# Sheet1.net
KiCad netlist of a schematic drawn in Altium Designer
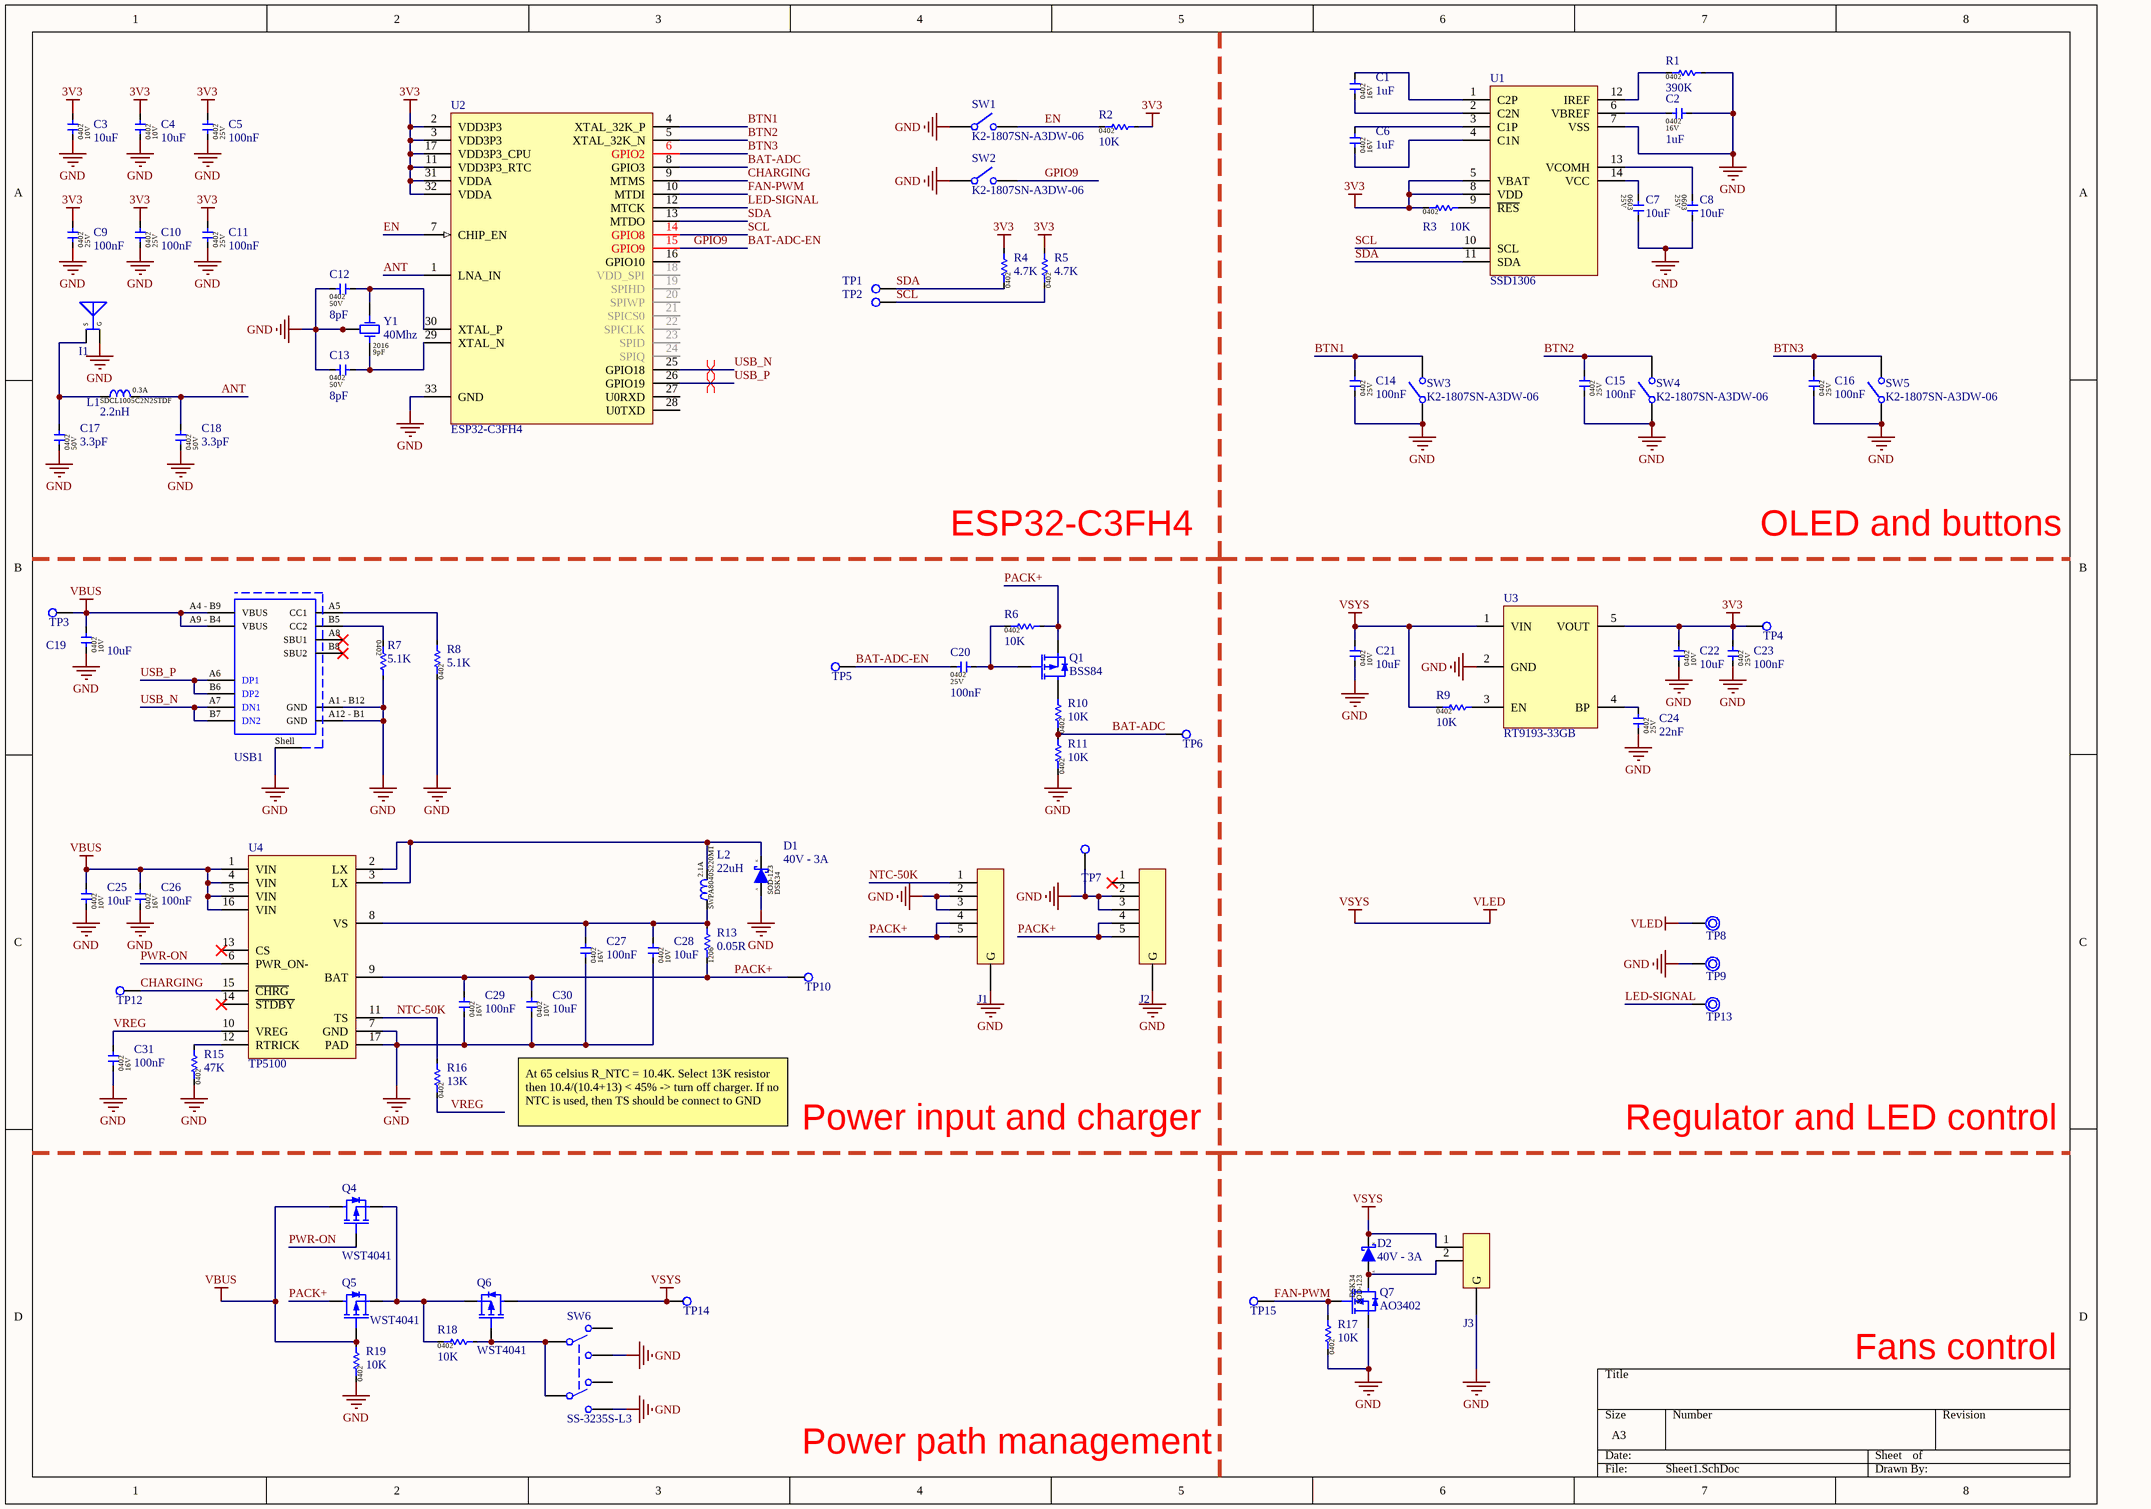
[diagram p0: Sheet1.SchDoc]

(export (version "E")
  (design (tool "Eeschema 10.0.6"))
  (components
    (comp (ref "C1")
      (value "1uF")
      (footprint "CAP-0402")
      (description "1uF ±10% 16V X5R 0402 Multilayer Ceramic Capacitors MLCC - SMD/SMT RoHS")
      (fields (field (name "MANUFACTURE PART") "0402X105K160CT") (field (name "VOLTAGE") "16V"))
      (libsource (lib "Capacitor Database") (part "Cap-non-polarized"))
    )
    (comp (ref "C2")
      (value "1uF")
      (footprint "CAP-0402")
      (description "1uF ±10% 16V X5R 0402 Multilayer Ceramic Capacitors MLCC - SMD/SMT RoHS")
      (fields (field (name "MANUFACTURE PART") "0402X105K160CT") (field (name "VOLTAGE") "16V"))
      (libsource (lib "Capacitor Database") (part "Cap-non-polarized"))
    )
    (comp (ref "C3")
      (value "10uF")
      (footprint "CAP-0402")
      (description "10V 10uF X5R ±20% 0402 Multilayer Ceramic Capacitors MLCC - SMD/SMT ROHS")
      (fields (field (name "MANUFACTURE PART") "CL05A106MP5NUNC") (field (name "VOLTAGE") "10V"))
      (libsource (lib "Capacitor Database") (part "Cap-non-polarized"))
    )
    (comp (ref "C4")
      (value "10uF")
      (footprint "CAP-0402")
      (description "10V 10uF X5R ±20% 0402 Multilayer Ceramic Capacitors MLCC - SMD/SMT ROHS")
      (fields (field (name "MANUFACTURE PART") "CL05A106MP5NUNC") (field (name "VOLTAGE") "10V"))
      (libsource (lib "Capacitor Database") (part "Cap-non-polarized"))
    )
    (comp (ref "C5")
      (value "100nF")
      (footprint "CAP-0402")
      (description "100nF ±10% 25V X5R 0402 Multilayer Ceramic Capacitors MLCC - SMD/SMT RoHS")
      (fields (field (name "MANUFACTURE PART") "0402X104K250CT") (field (name "VOLTAGE") "25V"))
      (libsource (lib "Capacitor Database") (part "Cap-non-polarized"))
    )
    (comp (ref "C6")
      (value "1uF")
      (footprint "CAP-0402")
      (description "1uF ±10% 16V X5R 0402 Multilayer Ceramic Capacitors MLCC - SMD/SMT RoHS")
      (fields (field (name "MANUFACTURE PART") "0402X105K160CT") (field (name "VOLTAGE") "16V"))
      (libsource (lib "Capacitor Database") (part "Cap-non-polarized"))
    )
    (comp (ref "C7")
      (value "10uF")
      (footprint "CAP-0603")
      (description "25V 10uF X5R ±20% 0603 Multilayer Ceramic Capacitors MLCC - SMD/SMT ROHS")
      (fields (field (name "MANUFACTURE PART") "CL10A106MA8NRNC") (field (name "VOLTAGE") "25V"))
      (libsource (lib "Capacitor Database") (part "Cap-non-polarized"))
    )
    (comp (ref "C8")
      (value "10uF")
      (footprint "CAP-0603")
      (description "25V 10uF X5R ±20% 0603 Multilayer Ceramic Capacitors MLCC - SMD/SMT ROHS")
      (fields (field (name "MANUFACTURE PART") "CL10A106MA8NRNC") (field (name "VOLTAGE") "25V"))
      (libsource (lib "Capacitor Database") (part "Cap-non-polarized"))
    )
    (comp (ref "C9")
      (value "100nF")
      (footprint "CAP-0402")
      (description "100nF ±10% 25V X5R 0402 Multilayer Ceramic Capacitors MLCC - SMD/SMT RoHS")
      (fields (field (name "MANUFACTURE PART") "0402X104K250CT") (field (name "VOLTAGE") "25V"))
      (libsource (lib "Capacitor Database") (part "Cap-non-polarized"))
    )
    (comp (ref "C10")
      (value "100nF")
      (footprint "CAP-0402")
      (description "100nF ±10% 25V X5R 0402 Multilayer Ceramic Capacitors MLCC - SMD/SMT RoHS")
      (fields (field (name "MANUFACTURE PART") "0402X104K250CT") (field (name "VOLTAGE") "25V"))
      (libsource (lib "Capacitor Database") (part "Cap-non-polarized"))
    )
    (comp (ref "C11")
      (value "100nF")
      (footprint "CAP-0402")
      (description "100nF ±10% 25V X5R 0402 Multilayer Ceramic Capacitors MLCC - SMD/SMT RoHS")
      (fields (field (name "MANUFACTURE PART") "0402X104K250CT") (field (name "VOLTAGE") "25V"))
      (libsource (lib "Capacitor Database") (part "Cap-non-polarized"))
    )
    (comp (ref "C12")
      (value "8pF")
      (footprint "CAP-0402")
      (description "8 pF ±0.5pF 50V Ceramic Capacitor C0G, NP0 0402 (1005 Metric)")
      (fields (field (name "MANUFACTURE PART") "CL05C080DB5NNNC") (field (name "VOLTAGE") "50V"))
      (libsource (lib "Capacitor Database") (part "Cap-non-polarized"))
    )
    (comp (ref "C13")
      (value "8pF")
      (footprint "CAP-0402")
      (description "8 pF ±0.5pF 50V Ceramic Capacitor C0G, NP0 0402 (1005 Metric)")
      (fields (field (name "MANUFACTURE PART") "CL05C080DB5NNNC") (field (name "VOLTAGE") "50V"))
      (libsource (lib "Capacitor Database") (part "Cap-non-polarized"))
    )
    (comp (ref "C14")
      (value "100nF")
      (footprint "CAP-0402")
      (description "100nF ±10% 25V X5R 0402 Multilayer Ceramic Capacitors MLCC - SMD/SMT RoHS")
      (fields (field (name "MANUFACTURE PART") "0402X104K250CT") (field (name "VOLTAGE") "25V"))
      (libsource (lib "Capacitor Database") (part "Cap-non-polarized"))
    )
    (comp (ref "C15")
      (value "100nF")
      (footprint "CAP-0402")
      (description "100nF ±10% 25V X5R 0402 Multilayer Ceramic Capacitors MLCC - SMD/SMT RoHS")
      (fields (field (name "MANUFACTURE PART") "0402X104K250CT") (field (name "VOLTAGE") "25V"))
      (libsource (lib "Capacitor Database") (part "Cap-non-polarized"))
    )
    (comp (ref "C16")
      (value "100nF")
      (footprint "CAP-0402")
      (description "100nF ±10% 25V X5R 0402 Multilayer Ceramic Capacitors MLCC - SMD/SMT RoHS")
      (fields (field (name "MANUFACTURE PART") "0402X104K250CT") (field (name "VOLTAGE") "25V"))
      (libsource (lib "Capacitor Database") (part "Cap-non-polarized"))
    )
    (comp (ref "C17")
      (value "3.3pF")
      (footprint "CAP-0402")
      (description "3.3pF ±0.25pF 50V NP0(C0G) 0402 Multilayer Ceramic Capacitors MLCC - SMD/SMT RoHS")
      (fields (field (name "MANUFACTURE PART") "0402N3R3C500CT") (field (name "VOLTAGE") "50V"))
      (libsource (lib "Capacitor Database") (part "Cap-non-polarized"))
    )
    (comp (ref "C18")
      (value "3.3pF")
      (footprint "CAP-0402")
      (description "3.3pF ±0.25pF 50V NP0(C0G) 0402 Multilayer Ceramic Capacitors MLCC - SMD/SMT RoHS")
      (fields (field (name "MANUFACTURE PART") "0402N3R3C500CT") (field (name "VOLTAGE") "50V"))
      (libsource (lib "Capacitor Database") (part "Cap-non-polarized"))
    )
    (comp (ref "C19")
      (value "10uF")
      (footprint "CAP-0402")
      (description "10V 10uF X5R ±20% 0402 Multilayer Ceramic Capacitors MLCC - SMD/SMT ROHS")
      (fields (field (name "MANUFACTURE PART") "CL05A106MP5NUNC") (field (name "VOLTAGE") "10V"))
      (libsource (lib "Capacitor Database") (part "Cap-non-polarized"))
    )
    (comp (ref "C20")
      (value "100nF")
      (footprint "CAP-0402")
      (description "100nF ±10% 25V X5R 0402 Multilayer Ceramic Capacitors MLCC - SMD/SMT RoHS")
      (fields (field (name "MANUFACTURE PART") "0402X104K250CT") (field (name "VOLTAGE") "25V"))
      (libsource (lib "Capacitor Database") (part "Cap-non-polarized"))
    )
    (comp (ref "C21")
      (value "10uF")
      (footprint "CAP-0402")
      (description "10V 10uF X5R ±20% 0402 Multilayer Ceramic Capacitors MLCC - SMD/SMT ROHS")
      (fields (field (name "MANUFACTURE PART") "CL05A106MP5NUNC") (field (name "VOLTAGE") "10V"))
      (libsource (lib "Capacitor Database") (part "Cap-non-polarized"))
    )
    (comp (ref "C22")
      (value "10uF")
      (footprint "CAP-0402")
      (description "10V 10uF X5R ±20% 0402 Multilayer Ceramic Capacitors MLCC - SMD/SMT ROHS")
      (fields (field (name "MANUFACTURE PART") "CL05A106MP5NUNC") (field (name "VOLTAGE") "10V"))
      (libsource (lib "Capacitor Database") (part "Cap-non-polarized"))
    )
    (comp (ref "C23")
      (value "100nF")
      (footprint "CAP-0402")
      (description "100nF ±10% 25V X5R 0402 Multilayer Ceramic Capacitors MLCC - SMD/SMT RoHS")
      (fields (field (name "MANUFACTURE PART") "0402X104K250CT") (field (name "VOLTAGE") "25V"))
      (libsource (lib "Capacitor Database") (part "Cap-non-polarized"))
    )
    (comp (ref "C24")
      (value "22nF")
      (footprint "CAP-0402")
      (description "22nF ±10% 25V X7R 0402 Multilayer Ceramic Capacitors MLCC - SMD/SMT RoHS")
      (fields (field (name "MANUFACTURE PART") "0402B223K250CT") (field (name "VOLTAGE") "25V"))
      (libsource (lib "Capacitor Database") (part "Cap-non-polarized"))
    )
    (comp (ref "C25")
      (value "10uF")
      (footprint "CAP-0402")
      (description "10V 10uF X5R ±20% 0402 Multilayer Ceramic Capacitors MLCC - SMD/SMT ROHS")
      (fields (field (name "MANUFACTURE PART") "CL05A106MP5NUNC") (field (name "VOLTAGE") "10V"))
      (libsource (lib "Capacitor Database") (part "Cap-non-polarized"))
    )
    (comp (ref "C26")
      (value "100nF")
      (footprint "CAP-0402")
      (description "100nF ±10% 16V X7R 0402 Multilayer Ceramic Capacitors MLCC - SMD/SMT RoHS")
      (fields (field (name "MANUFACTURE PART") "0402B104K160CT") (field (name "VOLTAGE") "16V"))
      (libsource (lib "Capacitor Database") (part "Cap-non-polarized"))
    )
    (comp (ref "C27")
      (value "100nF")
      (footprint "CAP-0402")
      (description "100nF ±10% 16V X7R 0402 Multilayer Ceramic Capacitors MLCC - SMD/SMT RoHS")
      (fields (field (name "MANUFACTURE PART") "0402B104K160CT") (field (name "VOLTAGE") "16V"))
      (libsource (lib "Capacitor Database") (part "Cap-non-polarized"))
    )
    (comp (ref "C28")
      (value "10uF")
      (footprint "CAP-0402")
      (description "10V 10uF X5R ±20% 0402 Multilayer Ceramic Capacitors MLCC - SMD/SMT ROHS")
      (fields (field (name "MANUFACTURE PART") "CL05A106MP5NUNC") (field (name "VOLTAGE") "10V"))
      (libsource (lib "Capacitor Database") (part "Cap-non-polarized"))
    )
    (comp (ref "C29")
      (value "100nF")
      (footprint "CAP-0402")
      (description "100nF ±10% 16V X7R 0402 Multilayer Ceramic Capacitors MLCC - SMD/SMT RoHS")
      (fields (field (name "MANUFACTURE PART") "0402B104K160CT") (field (name "VOLTAGE") "16V"))
      (libsource (lib "Capacitor Database") (part "Cap-non-polarized"))
    )
    (comp (ref "C30")
      (value "10uF")
      (footprint "CAP-0402")
      (description "10V 10uF X5R ±20% 0402 Multilayer Ceramic Capacitors MLCC - SMD/SMT ROHS")
      (fields (field (name "MANUFACTURE PART") "CL05A106MP5NUNC") (field (name "VOLTAGE") "10V"))
      (libsource (lib "Capacitor Database") (part "Cap-non-polarized"))
    )
    (comp (ref "C31")
      (value "100nF")
      (footprint "CAP-0402")
      (description "100nF ±10% 16V X7R 0402 Multilayer Ceramic Capacitors MLCC - SMD/SMT RoHS")
      (fields (field (name "MANUFACTURE PART") "0402B104K160CT") (field (name "VOLTAGE") "16V"))
      (libsource (lib "Capacitor Database") (part "Cap-non-polarized"))
    )
    (comp (ref "D1")
      (value "40V - 3A")
      (footprint "SOD123")
      (description "40V 3A 550mV @ 3A SOD-123 Schottky Barrier Diodes (SBD) RoHS")
      (fields (field (name "MANUFACTURE PART") "DSK34"))
      (libsource (lib "Diode Database") (part "Schottky diode"))
    )
    (comp (ref "D2")
      (value "40V - 3A")
      (footprint "SOD123")
      (description "40V 3A 550mV @ 3A SOD-123 Schottky Barrier Diodes (SBD) RoHS")
      (fields (field (name "MANUFACTURE PART") "DSK34"))
      (libsource (lib "Diode Database") (part "Schottky diode"))
    )
    (comp (ref "I1")
      (value "AN043")
      (footprint "PCB antenna - AN043")
      (description ".Description")
      (libsource (lib "Connectors, Misc") (part "Ipex"))
    )
    (comp (ref "J1")
      (value "20037WR-05")
      (footprint "HY-2.0-5Pin-SMT")
      (description ".Description")
      (libsource (lib "Connectors, Misc") (part "Conn-5P_PAD"))
    )
    (comp (ref "J2")
      (value "20037WR-05")
      (footprint "HY-2.0-5Pin-SMT")
      (description ".Description")
      (libsource (lib "Connectors, Misc") (part "Conn-5P_PAD"))
    )
    (comp (ref "J3")
      (value "ZX-XH2.54-2PLT")
      (footprint "XH-2.54-2Pin-SMT-vertical")
      (description ".Description")
      (libsource (lib "Connectors, Misc") (part "Conn-2P_PAD"))
    )
    (comp (ref "L1")
      (value "2.2nH")
      (footprint "L-0402")
      (description "300mA 2.2nH 200mΩ 0402 Inductors (SMD) ROHS")
      (fields (field (name "MANUFACTURE PART") "SDCL1005C2N2STDF"))
      (libsource (lib "Inductor Database") (part "Inductor"))
    )
    (comp (ref "L2")
      (value "22uH")
      (footprint "IND-8040")
      (description "Inductor 22uH ±20% 2.1A, 8.0x8.0x4.0")
      (fields (field (name "MANUFACTURE PART") "SWPA8040S220MT"))
      (libsource (lib "") (part "Inductor_1"))
    )
    (comp (ref "Q1")
      (value "BSS84")
      (footprint "SOT23-3")
      (description "60V 0.23A 3.5Ω@10V,230mA 350mW 1V@230mA 1PCSPChannel SOT-23 MOSFETs ROHS")
      (libsource (lib "Transistor Database") (part "Generic P-Mosfet"))
    )
    (comp (ref "Q4")
      (value "WST4041")
      (footprint "SOT23-3")
      (description "1.4W 40V 6A 2.2V 250uA P Channel 0.04Ω 3A,10V SOT-23(SOT-23-3) MOSFETs ROHS")
      (libsource (lib "Transistor Database") (part "Generic P-Mosfet"))
    )
    (comp (ref "Q5")
      (value "WST4041")
      (footprint "SOT23-3")
      (description "1.4W 40V 6A 2.2V 250uA P Channel 0.04Ω 3A,10V SOT-23(SOT-23-3) MOSFETs ROHS")
      (libsource (lib "Transistor Database") (part "Generic P-Mosfet"))
    )
    (comp (ref "Q6")
      (value "WST4041")
      (footprint "SOT23-3")
      (description "1.4W 40V 6A 2.2V 250uA P Channel 0.04Ω 3A,10V SOT-23(SOT-23-3) MOSFETs ROHS")
      (libsource (lib "Transistor Database") (part "Generic P-Mosfet"))
    )
    (comp (ref "Q7")
      (value "AO3402")
      (footprint "SOT23-3")
      (description "N-Channel 30V 4A 1.4V @ 250uA 55mΩ @ 4A,10V 1.4W SOT-23 MOSFETs RoHS")
      (libsource (lib "Transistor Database") (part "Generic N-Mosfet"))
    )
    (comp (ref "R1")
      (value "390K")
      (footprint "RES-0402")
      (description "±1% 1/16W 50V ±100ppm/℃ -55℃~+155℃ 390kΩ 0402 Chip Resistor - Surface Mount ROHS")
      (fields (field (name "MANUFACTURE PART") "WR04X3903FTL"))
      (libsource (lib "Resistor Database") (part "Resistor"))
    )
    (comp (ref "R2")
      (value "10K")
      (footprint "RES-0402")
      (description "10kΩ ±1% 1/16W ±100ppm/℃ 0402 Chip Resistor - Surface Mount RoHS")
      (fields (field (name "MANUFACTURE PART") "WR04X1002FTL"))
      (libsource (lib "Resistor Database") (part "Resistor"))
    )
    (comp (ref "R3")
      (value "10K")
      (footprint "RES-0402")
      (description "10kΩ ±1% 1/16W ±100ppm/℃ 0402 Chip Resistor - Surface Mount RoHS")
      (fields (field (name "MANUFACTURE PART") "WR04X1002FTL"))
      (libsource (lib "Resistor Database") (part "Resistor"))
    )
    (comp (ref "R4")
      (value "4.7K")
      (footprint "RES-0402")
      (description "4.7kΩ ±1% 1/16W ±100ppm/℃ 0402 Chip Resistor - Surface Mount RoHS")
      (fields (field (name "MANUFACTURE PART") "WR04X4701FTL"))
      (libsource (lib "Resistor Database") (part "Resistor"))
    )
    (comp (ref "R5")
      (value "4.7K")
      (footprint "RES-0402")
      (description "4.7kΩ ±1% 1/16W ±100ppm/℃ 0402 Chip Resistor - Surface Mount RoHS")
      (fields (field (name "MANUFACTURE PART") "WR04X4701FTL"))
      (libsource (lib "Resistor Database") (part "Resistor"))
    )
    (comp (ref "R6")
      (value "10K")
      (footprint "RES-0402")
      (description "10kΩ ±1% 1/16W ±100ppm/℃ 0402 Chip Resistor - Surface Mount RoHS")
      (fields (field (name "MANUFACTURE PART") "WR04X1002FTL"))
      (libsource (lib "Resistor Database") (part "Resistor"))
    )
    (comp (ref "R7")
      (value "5.1K")
      (footprint "RES-0402")
      (description "5.1kΩ ±1% 1/16W ±100ppm/℃ 0402 Chip Resistor - Surface Mount RoHS")
      (fields (field (name "MANUFACTURE PART") "WR04X5101FTL"))
      (libsource (lib "Resistor Database") (part "Resistor"))
    )
    (comp (ref "R8")
      (value "5.1K")
      (footprint "RES-0402")
      (description "5.1kΩ ±1% 1/16W ±100ppm/℃ 0402 Chip Resistor - Surface Mount RoHS")
      (fields (field (name "MANUFACTURE PART") "WR04X5101FTL"))
      (libsource (lib "Resistor Database") (part "Resistor"))
    )
    (comp (ref "R9")
      (value "10K")
      (footprint "RES-0402")
      (description "10kΩ ±1% 1/16W ±100ppm/℃ 0402 Chip Resistor - Surface Mount RoHS")
      (fields (field (name "MANUFACTURE PART") "WR04X1002FTL"))
      (libsource (lib "Resistor Database") (part "Resistor"))
    )
    (comp (ref "R10")
      (value "10K")
      (footprint "RES-0402")
      (description "10kΩ ±1% 1/16W ±100ppm/℃ 0402 Chip Resistor - Surface Mount RoHS")
      (fields (field (name "MANUFACTURE PART") "WR04X1002FTL"))
      (libsource (lib "Resistor Database") (part "Resistor"))
    )
    (comp (ref "R11")
      (value "10K")
      (footprint "RES-0402")
      (description "10kΩ ±1% 1/16W ±100ppm/℃ 0402 Chip Resistor - Surface Mount RoHS")
      (fields (field (name "MANUFACTURE PART") "WR04X1002FTL"))
      (libsource (lib "Resistor Database") (part "Resistor"))
    )
    (comp (ref "R13")
      (value "0.05R")
      (footprint "RES-1206")
      (description "±1% 0.05Ω 1W ±50ppm/℃ 1206 Current Sense Resistors/Shunt Resistors ROHS")
      (fields (field (name "MANUFACTURE PART") "LR1206-21R050F4"))
      (libsource (lib "Resistor Database") (part "Resistor"))
    )
    (comp (ref "R15")
      (value "47K")
      (footprint "RES-0402")
      (description "62.5mW Thick Film Resistors ±100ppm/℃ ±1% 47kΩ 0402 Chip Resistor - Surface Mount ROHS")
      (fields (field (name "MANUFACTURE PART") "RC0402FR-0747KL"))
      (libsource (lib "Resistor Database") (part "Resistor"))
    )
    (comp (ref "R16")
      (value "13K")
      (footprint "RES-0402")
      (description "62.5mW Thick Film Resistors ±100ppm/℃ ±1% 13kΩ 0402 Chip Resistor - Surface Mount ROHS")
      (fields (field (name "MANUFACTURE PART") "RC0402FR-0713KL"))
      (libsource (lib "Resistor Database") (part "Resistor"))
    )
    (comp (ref "R17")
      (value "10K")
      (footprint "RES-0402")
      (description "10kΩ ±1% 1/16W ±100ppm/℃ 0402 Chip Resistor - Surface Mount RoHS")
      (fields (field (name "MANUFACTURE PART") "WR04X1002FTL"))
      (libsource (lib "Resistor Database") (part "Resistor"))
    )
    (comp (ref "R18")
      (value "10K")
      (footprint "RES-0402")
      (description "10kΩ ±1% 1/16W ±100ppm/℃ 0402 Chip Resistor - Surface Mount RoHS")
      (fields (field (name "MANUFACTURE PART") "WR04X1002FTL"))
      (libsource (lib "Resistor Database") (part "Resistor"))
    )
    (comp (ref "R19")
      (value "10K")
      (footprint "RES-0402")
      (description "10kΩ ±1% 1/16W ±100ppm/℃ 0402 Chip Resistor - Surface Mount RoHS")
      (fields (field (name "MANUFACTURE PART") "WR04X1002FTL"))
      (libsource (lib "Resistor Database") (part "Resistor"))
    )
    (comp (ref "SW1")
      (value "K2-1807SN-A3DW-06")
      (footprint "SW - TYPE 3")
      (description ".Description")
      (libsource (lib "Connectors, Misc") (part "Tactile Switch"))
    )
    (comp (ref "SW2")
      (value "K2-1807SN-A3DW-06")
      (footprint "SW - TYPE 3")
      (description ".Description")
      (libsource (lib "Connectors, Misc") (part "Tactile Switch"))
    )
    (comp (ref "SW3")
      (value "K2-1807SN-A3DW-06")
      (footprint "SW - TYPE 3")
      (description ".Description")
      (libsource (lib "Connectors, Misc") (part "Tactile Switch"))
    )
    (comp (ref "SW4")
      (value "K2-1807SN-A3DW-06")
      (footprint "SW - TYPE 3")
      (description ".Description")
      (libsource (lib "Connectors, Misc") (part "Tactile Switch"))
    )
    (comp (ref "SW5")
      (value "K2-1807SN-A3DW-06")
      (footprint "SW - TYPE 3")
      (description ".Description")
      (libsource (lib "Connectors, Misc") (part "Tactile Switch"))
    )
    (comp (ref "SW6")
      (value "SS-3235S-L3")
      (footprint "DPDT - type 1")
      (description ".Description")
      (libsource (lib "Connectors, Misc") (part "DPDT switch"))
    )
    (comp (ref "TP1")
      (value "Test point")
      (footprint "Test point")
      (description ".Description")
      (libsource (lib "Connectors, Misc") (part "Test point"))
    )
    (comp (ref "TP2")
      (value "Test point")
      (footprint "Test point")
      (description ".Description")
      (libsource (lib "Connectors, Misc") (part "Test point"))
    )
    (comp (ref "TP3")
      (value "Test point")
      (footprint "Test point")
      (description ".Description")
      (libsource (lib "Connectors, Misc") (part "Test point"))
    )
    (comp (ref "TP4")
      (value "Test point")
      (footprint "Test point")
      (description ".Description")
      (libsource (lib "Connectors, Misc") (part "Test point"))
    )
    (comp (ref "TP5")
      (value "Test point")
      (footprint "Test point")
      (description ".Description")
      (libsource (lib "Connectors, Misc") (part "Test point"))
    )
    (comp (ref "TP6")
      (value "Test point")
      (footprint "Test point")
      (description ".Description")
      (libsource (lib "Connectors, Misc") (part "Test point"))
    )
    (comp (ref "TP7")
      (value "Test point")
      (footprint "Test point")
      (description ".Description")
      (libsource (lib "Connectors, Misc") (part "Test point"))
    )
    (comp (ref "TP8")
      (value "Test point hole")
      (footprint "Test point hole")
      (description ".Description")
      (libsource (lib "Connectors, Misc") (part "Test point hole"))
    )
    (comp (ref "TP9")
      (value "Test point hole")
      (footprint "Test point hole")
      (description ".Description")
      (libsource (lib "Connectors, Misc") (part "Test point hole"))
    )
    (comp (ref "TP10")
      (value "Test point")
      (footprint "Test point")
      (description ".Description")
      (libsource (lib "Connectors, Misc") (part "Test point"))
    )
    (comp (ref "TP12")
      (value "Test point")
      (footprint "Test point")
      (description ".Description")
      (libsource (lib "Connectors, Misc") (part "Test point"))
    )
    (comp (ref "TP13")
      (value "Test point hole")
      (footprint "Test point hole")
      (description ".Description")
      (libsource (lib "Connectors, Misc") (part "Test point hole"))
    )
    (comp (ref "TP14")
      (value "Test point")
      (footprint "Test point")
      (description ".Description")
      (libsource (lib "Connectors, Misc") (part "Test point"))
    )
    (comp (ref "TP15")
      (value "Test point")
      (footprint "Test point")
      (description ".Description")
      (libsource (lib "Connectors, Misc") (part "Test point"))
    )
    (comp (ref "U1")
      (value "SSD1306")
      (footprint "OLED 0.91 14P")
      (description ".Description")
      (libsource (lib "Connectors, Misc") (part "OLED_0.91_SSD1306"))
    )
    (comp (ref "U2")
      (value "ESP32-C3FH4")
      (footprint "QFN32-5X5MM_PAD")
      (libsource (lib "IC Database") (part "ESP32-C3FH4"))
    )
    (comp (ref "U3")
      (value "RT9193-33GB")
      (footprint "SOT23-5")
      (description "Fixed 5.5V 3.3V 300mV @ 300mA SOT-23-5 Dropout Regulators(LDO) RoHS")
      (libsource (lib "Regulator Database") (part "RT9193"))
    )
    (comp (ref "U4")
      (value "TP5100")
      (footprint "QFN16-4X4MM_PAD")
      (description "1 and 2 cell Li-lon Battery Charger")
      (libsource (lib "IC Database") (part "TP5100"))
    )
    (comp (ref "USB1")
      (value "918-418K2023S40001")
      (footprint "1 FEMALE USB -C 16")
      (description ".Description")
      (libsource (lib "Connectors, Misc") (part "Female USB-C 16"))
    )
    (comp (ref "Y1")
      (value "40Mhz")
      (footprint "Crystal-2016")
      (description "40MHz 9pF SMD2016-4P Crystals ROHS")
      (fields (field (name "MANUFACTURE PART") "TZ1269D"))
      (libsource (lib "Osc Database") (part "XTAL-4 pin"))
    )
  )
  (nets
    (net (code "1") (name "/ANT") (class "Default")
      (node (ref "C18") (pin "2") (pinfunction "2_2") (pintype "passive"))
      (node (ref "L1") (pin "2") (pinfunction "2_2") (pintype "passive"))
      (node (ref "U2") (pin "1") (pinfunction "LNA_IN_1") (pintype "passive"))
    )
    (net (code "2") (name "/BAT-ADC") (class "Default")
      (node (ref "R10") (pin "1") (pinfunction "1_1") (pintype "passive"))
      (node (ref "R11") (pin "2") (pinfunction "2_2") (pintype "passive"))
      (node (ref "TP6") (pin "1") (pinfunction "1_1") (pintype "passive"))
      (node (ref "U2") (pin "8") (pinfunction "GPIO3_8") (pintype "passive"))
    )
    (net (code "3") (name "/BAT-ADC-EN") (class "Default")
      (node (ref "C20") (pin "1") (pinfunction "1_1") (pintype "passive"))
      (node (ref "SW2") (pin "2") (pintype "passive"))
      (node (ref "TP5") (pin "1") (pinfunction "1_1") (pintype "passive"))
      (node (ref "U2") (pin "15") (pinfunction "GPIO9_15") (pintype "passive"))
    )
    (net (code "4") (name "/BTN1") (class "Default")
      (node (ref "C14") (pin "2") (pinfunction "2_2") (pintype "passive"))
      (node (ref "SW3") (pin "2") (pintype "passive"))
      (node (ref "U2") (pin "4") (pinfunction "XTAL_32K_P_4") (pintype "passive"))
    )
    (net (code "5") (name "/BTN2") (class "Default")
      (node (ref "C15") (pin "2") (pinfunction "2_2") (pintype "passive"))
      (node (ref "SW4") (pin "2") (pintype "passive"))
      (node (ref "U2") (pin "5") (pinfunction "XTAL_32K_N_5") (pintype "passive"))
    )
    (net (code "6") (name "/BTN3") (class "Default")
      (node (ref "C16") (pin "2") (pinfunction "2_2") (pintype "passive"))
      (node (ref "SW5") (pin "2") (pintype "passive"))
      (node (ref "U2") (pin "6") (pinfunction "GPIO2_6") (pintype "passive"))
    )
    (net (code "7") (name "/CHARGING") (class "Default")
      (node (ref "TP12") (pin "1") (pinfunction "1_1") (pintype "passive"))
      (node (ref "U2") (pin "9") (pinfunction "MTMS_9") (pintype "passive"))
      (node (ref "U4") (pin "15") (pinfunction "~{CHRG}_15") (pintype "passive"))
    )
    (net (code "8") (name "/EN") (class "Default")
      (node (ref "R2") (pin "1") (pinfunction "1_1") (pintype "passive"))
      (node (ref "SW1") (pin "2") (pintype "passive"))
      (node (ref "U2") (pin "7") (pinfunction "CHIP_EN_7") (pintype "input"))
    )
    (net (code "9") (name "/FAN-PWM") (class "Default")
      (node (ref "Q7") (pin "1") (pinfunction "G_1") (pintype "passive"))
      (node (ref "R17") (pin "2") (pinfunction "2_2") (pintype "passive"))
      (node (ref "TP15") (pin "1") (pinfunction "1_1") (pintype "passive"))
      (node (ref "U2") (pin "10") (pinfunction "MTDI_10") (pintype "passive"))
    )
    (net (code "10") (name "/LED-SIGNAL") (class "Default")
      (node (ref "TP13") (pin "1") (pinfunction "1_1") (pintype "passive"))
      (node (ref "U2") (pin "12") (pinfunction "MTCK_12") (pintype "passive"))
    )
    (net (code "11") (name "/NTC-50K") (class "Default")
      (node (ref "J1") (pin "1") (pinfunction "1_1") (pintype "passive"))
      (node (ref "R16") (pin "2") (pinfunction "2_2") (pintype "passive"))
      (node (ref "U4") (pin "11") (pinfunction "TS_11") (pintype "passive"))
    )
    (net (code "12") (name "/PACK+") (class "Default")
      (node (ref "C29") (pin "2") (pinfunction "2_2") (pintype "passive"))
      (node (ref "C30") (pin "2") (pinfunction "2_2") (pintype "passive"))
      (node (ref "J1") (pin "4") (pinfunction "4_4") (pintype "passive"))
      (node (ref "J1") (pin "5") (pinfunction "5_5") (pintype "passive"))
      (node (ref "J2") (pin "4") (pinfunction "4_4") (pintype "passive"))
      (node (ref "J2") (pin "5") (pinfunction "5_5") (pintype "passive"))
      (node (ref "Q1") (pin "2") (pinfunction "S_2") (pintype "passive"))
      (node (ref "Q5") (pin "3") (pinfunction "D_3") (pintype "passive"))
      (node (ref "R13") (pin "1") (pinfunction "1_1") (pintype "passive"))
      (node (ref "R6") (pin "2") (pinfunction "2_2") (pintype "passive"))
      (node (ref "TP10") (pin "1") (pinfunction "1_1") (pintype "passive"))
      (node (ref "U4") (pin "9") (pinfunction "BAT_9") (pintype "passive"))
    )
    (net (code "13") (name "/PWR-ON") (class "Default")
      (node (ref "Q4") (pin "1") (pinfunction "G_1") (pintype "passive"))
      (node (ref "U4") (pin "6") (pinfunction "PWR_ON-_6") (pintype "passive"))
    )
    (net (code "14") (name "/SCL") (class "Default")
      (node (ref "R5") (pin "1") (pinfunction "1_1") (pintype "passive"))
      (node (ref "TP2") (pin "1") (pinfunction "1_1") (pintype "passive"))
      (node (ref "U1") (pin "10") (pinfunction "SCL_10") (pintype "passive"))
      (node (ref "U2") (pin "14") (pinfunction "GPIO8_14") (pintype "passive"))
    )
    (net (code "15") (name "/SDA") (class "Default")
      (node (ref "R4") (pin "1") (pinfunction "1_1") (pintype "passive"))
      (node (ref "TP1") (pin "1") (pinfunction "1_1") (pintype "passive"))
      (node (ref "U1") (pin "11") (pinfunction "SDA_11") (pintype "passive"))
      (node (ref "U2") (pin "13") (pinfunction "MTDO_13") (pintype "passive"))
    )
    (net (code "16") (name "/USB_N") (class "Default")
      (node (ref "U2") (pin "25") (pinfunction "GPIO18_25") (pintype "passive"))
      (node (ref "USB1") (pin "A7") (pinfunction "DN1_A7") (pintype "passive"))
      (node (ref "USB1") (pin "B7") (pinfunction "DN2_B7") (pintype "passive"))
    )
    (net (code "17") (name "/USB_P") (class "Default")
      (node (ref "U2") (pin "26") (pinfunction "GPIO19_26") (pintype "passive"))
      (node (ref "USB1") (pin "A6") (pinfunction "DP1_A6") (pintype "passive"))
      (node (ref "USB1") (pin "B6") (pinfunction "DP2_B6") (pintype "passive"))
    )
    (net (code "18") (name "/VREG") (class "Default")
      (node (ref "C31") (pin "2") (pinfunction "2_2") (pintype "passive"))
      (node (ref "R16") (pin "1") (pinfunction "1_1") (pintype "passive"))
      (node (ref "U4") (pin "10") (pinfunction "VREG_10") (pintype "passive"))
    )
    (net (code "19") (name "3V3") (class "Default")
      (node (ref "C10") (pin "2") (pinfunction "2_2") (pintype "passive"))
      (node (ref "C11") (pin "2") (pinfunction "2_2") (pintype "passive"))
      (node (ref "C22") (pin "2") (pinfunction "2_2") (pintype "passive"))
      (node (ref "C23") (pin "2") (pinfunction "2_2") (pintype "passive"))
      (node (ref "C3") (pin "2") (pinfunction "2_2") (pintype "passive"))
      (node (ref "C4") (pin "2") (pinfunction "2_2") (pintype "passive"))
      (node (ref "C5") (pin "2") (pinfunction "2_2") (pintype "passive"))
      (node (ref "C9") (pin "2") (pinfunction "2_2") (pintype "passive"))
      (node (ref "R2") (pin "2") (pinfunction "2_2") (pintype "passive"))
      (node (ref "R3") (pin "1") (pinfunction "1_1") (pintype "passive"))
      (node (ref "R4") (pin "2") (pinfunction "2_2") (pintype "passive"))
      (node (ref "R5") (pin "2") (pinfunction "2_2") (pintype "passive"))
      (node (ref "TP4") (pin "1") (pinfunction "1_1") (pintype "passive"))
      (node (ref "U1") (pin "5") (pinfunction "VBAT_5") (pintype "passive"))
      (node (ref "U1") (pin "8") (pinfunction "VDD_8") (pintype "passive"))
      (node (ref "U2") (pin "11") (pinfunction "VDD3P3_RTC_11") (pintype "passive"))
      (node (ref "U2") (pin "17") (pinfunction "VDD3P3_CPU_17") (pintype "passive"))
      (node (ref "U2") (pin "2") (pinfunction "VDD3P3_2") (pintype "passive"))
      (node (ref "U2") (pin "3") (pinfunction "VDD3P3_3") (pintype "passive"))
      (node (ref "U2") (pin "31") (pinfunction "VDDA_31") (pintype "passive"))
      (node (ref "U2") (pin "32") (pinfunction "VDDA_32") (pintype "passive"))
      (node (ref "U3") (pin "5") (pinfunction "VOUT_5") (pintype "passive"))
    )
    (net (code "20") (name "GND") (class "Default")
      (node (ref "C10") (pin "1") (pinfunction "1_1") (pintype "passive"))
      (node (ref "C11") (pin "1") (pinfunction "1_1") (pintype "passive"))
      (node (ref "C12") (pin "1") (pinfunction "1_1") (pintype "passive"))
      (node (ref "C13") (pin "1") (pinfunction "1_1") (pintype "passive"))
      (node (ref "C14") (pin "1") (pinfunction "1_1") (pintype "passive"))
      (node (ref "C15") (pin "1") (pinfunction "1_1") (pintype "passive"))
      (node (ref "C16") (pin "1") (pinfunction "1_1") (pintype "passive"))
      (node (ref "C17") (pin "1") (pinfunction "1_1") (pintype "passive"))
      (node (ref "C18") (pin "1") (pinfunction "1_1") (pintype "passive"))
      (node (ref "C19") (pin "1") (pinfunction "1_1") (pintype "passive"))
      (node (ref "C2") (pin "2") (pinfunction "2_2") (pintype "passive"))
      (node (ref "C21") (pin "1") (pinfunction "1_1") (pintype "passive"))
      (node (ref "C22") (pin "1") (pinfunction "1_1") (pintype "passive"))
      (node (ref "C23") (pin "1") (pinfunction "1_1") (pintype "passive"))
      (node (ref "C24") (pin "1") (pinfunction "1_1") (pintype "passive"))
      (node (ref "C25") (pin "1") (pinfunction "1_1") (pintype "passive"))
      (node (ref "C26") (pin "1") (pinfunction "1_1") (pintype "passive"))
      (node (ref "C27") (pin "1") (pinfunction "1_1") (pintype "passive"))
      (node (ref "C28") (pin "1") (pinfunction "1_1") (pintype "passive"))
      (node (ref "C29") (pin "1") (pinfunction "1_1") (pintype "passive"))
      (node (ref "C3") (pin "1") (pinfunction "1_1") (pintype "passive"))
      (node (ref "C30") (pin "1") (pinfunction "1_1") (pintype "passive"))
      (node (ref "C31") (pin "1") (pinfunction "1_1") (pintype "passive"))
      (node (ref "C4") (pin "1") (pinfunction "1_1") (pintype "passive"))
      (node (ref "C5") (pin "1") (pinfunction "1_1") (pintype "passive"))
      (node (ref "C7") (pin "2") (pinfunction "2_2") (pintype "passive"))
      (node (ref "C8") (pin "2") (pinfunction "2_2") (pintype "passive"))
      (node (ref "C9") (pin "1") (pinfunction "1_1") (pintype "passive"))
      (node (ref "D1") (pin "2") (pinfunction "Anode_2") (pintype "passive"))
      (node (ref "I1") (pin "0") (pinfunction "G_0") (pintype "passive"))
      (node (ref "J1") (pin "0") (pinfunction "G_0") (pintype "passive"))
      (node (ref "J1") (pin "2") (pinfunction "2_2") (pintype "passive"))
      (node (ref "J1") (pin "3") (pinfunction "3_3") (pintype "passive"))
      (node (ref "J2") (pin "0") (pinfunction "G_0") (pintype "passive"))
      (node (ref "J2") (pin "2") (pinfunction "2_2") (pintype "passive"))
      (node (ref "J2") (pin "3") (pinfunction "3_3") (pintype "passive"))
      (node (ref "J3") (pin "0") (pinfunction "G_0") (pintype "passive"))
      (node (ref "Q7") (pin "2") (pinfunction "S_2") (pintype "passive"))
      (node (ref "R1") (pin "2") (pinfunction "2_2") (pintype "passive"))
      (node (ref "R11") (pin "1") (pinfunction "1_1") (pintype "passive"))
      (node (ref "R15") (pin "1") (pinfunction "1_1") (pintype "passive"))
      (node (ref "R17") (pin "1") (pinfunction "1_1") (pintype "passive"))
      (node (ref "R19") (pin "1") (pinfunction "1_1") (pintype "passive"))
      (node (ref "R7") (pin "2") (pinfunction "2_2") (pintype "passive"))
      (node (ref "R8") (pin "1") (pinfunction "1_1") (pintype "passive"))
      (node (ref "SW1") (pin "1") (pintype "passive"))
      (node (ref "SW2") (pin "1") (pintype "passive"))
      (node (ref "SW3") (pin "1") (pintype "passive"))
      (node (ref "SW4") (pin "1") (pintype "passive"))
      (node (ref "SW5") (pin "1") (pintype "passive"))
      (node (ref "SW6") (pin "NO1") (pintype "passive"))
      (node (ref "SW6") (pin "NO2") (pintype "passive"))
      (node (ref "TP7") (pin "1") (pinfunction "1_1") (pintype "passive"))
      (node (ref "TP9") (pin "1") (pinfunction "1_1") (pintype "passive"))
      (node (ref "U1") (pin "7") (pinfunction "VSS_7") (pintype "passive"))
      (node (ref "U2") (pin "33") (pinfunction "GND_33") (pintype "passive"))
      (node (ref "U3") (pin "2") (pinfunction "GND_2") (pintype "passive"))
      (node (ref "U4") (pin "17") (pinfunction "PAD_17") (pintype "passive"))
      (node (ref "U4") (pin "7") (pinfunction "GND_7") (pintype "passive"))
      (node (ref "USB1") (pin "A12_-_B1") (pinfunction "GND_A12_-_B1") (pintype "passive"))
      (node (ref "USB1") (pin "A1_-_B12") (pinfunction "GND_A1_-_B12") (pintype "passive"))
      (node (ref "USB1") (pin "Shell") (pinfunction "Shield_Shell") (pintype "passive"))
      (node (ref "Y1") (pin "2") (pinfunction "GND_2") (pintype "power_in"))
      (node (ref "Y1") (pin "4") (pinfunction "GND_4") (pintype "power_in"))
    )
    (net (code "21") (name "Net-(D1-Cathode)") (class "Default")
      (node (ref "D1") (pin "1") (pinfunction "Cathode_1") (pintype "passive"))
      (node (ref "L2") (pin "2") (pinfunction "2_2") (pintype "passive"))
      (node (ref "U4") (pin "2") (pinfunction "LX_2") (pintype "passive"))
      (node (ref "U4") (pin "3") (pinfunction "LX_3") (pintype "passive"))
    )
    (net (code "22") (name "Net-(D2-Anode)") (class "Default")
      (node (ref "D2") (pin "2") (pinfunction "Anode_2") (pintype "passive"))
      (node (ref "J3") (pin "2") (pinfunction "2_2") (pintype "passive"))
      (node (ref "Q7") (pin "3") (pinfunction "D_3") (pintype "passive"))
    )
    (net (code "23") (name "Net-(I1-S)") (class "Default")
      (node (ref "C17") (pin "2") (pinfunction "2_2") (pintype "passive"))
      (node (ref "I1") (pin "1") (pinfunction "S_1") (pintype "passive"))
      (node (ref "L1") (pin "1") (pinfunction "1_1") (pintype "passive"))
    )
    (net (code "24") (name "Net-(Q1-D)") (class "Default")
      (node (ref "Q1") (pin "3") (pinfunction "D_3") (pintype "passive"))
      (node (ref "R10") (pin "2") (pinfunction "2_2") (pintype "passive"))
    )
    (net (code "25") (name "Net-(Q1-G)") (class "Default")
      (node (ref "C20") (pin "2") (pinfunction "2_2") (pintype "passive"))
      (node (ref "Q1") (pin "1") (pinfunction "G_1") (pintype "passive"))
      (node (ref "R6") (pin "1") (pinfunction "1_1") (pintype "passive"))
    )
    (net (code "26") (name "Net-(Q4-S)") (class "Default")
      (node (ref "Q4") (pin "2") (pinfunction "S_2") (pintype "passive"))
      (node (ref "Q5") (pin "2") (pinfunction "S_2") (pintype "passive"))
      (node (ref "Q6") (pin "2") (pinfunction "S_2") (pintype "passive"))
      (node (ref "R18") (pin "1") (pinfunction "1_1") (pintype "passive"))
    )
    (net (code "27") (name "Net-(Q6-G)") (class "Default")
      (node (ref "Q6") (pin "1") (pinfunction "G_1") (pintype "passive"))
      (node (ref "R18") (pin "2") (pinfunction "2_2") (pintype "passive"))
      (node (ref "SW6") (pin "COM1") (pintype "passive"))
      (node (ref "SW6") (pin "COM2") (pintype "passive"))
    )
    (net (code "28") (name "Net-(U1-C1N)") (class "Default")
      (node (ref "C6") (pin "1") (pinfunction "1_1") (pintype "passive"))
      (node (ref "U1") (pin "4") (pinfunction "C1N_4") (pintype "passive"))
    )
    (net (code "29") (name "Net-(U1-C1P)") (class "Default")
      (node (ref "C6") (pin "2") (pinfunction "2_2") (pintype "passive"))
      (node (ref "U1") (pin "3") (pinfunction "C1P_3") (pintype "passive"))
    )
    (net (code "30") (name "Net-(U1-C2N)") (class "Default")
      (node (ref "C1") (pin "1") (pinfunction "1_1") (pintype "passive"))
      (node (ref "U1") (pin "2") (pinfunction "C2N_2") (pintype "passive"))
    )
    (net (code "31") (name "Net-(U1-C2P)") (class "Default")
      (node (ref "C1") (pin "2") (pinfunction "2_2") (pintype "passive"))
      (node (ref "U1") (pin "1") (pinfunction "C2P_1") (pintype "passive"))
    )
    (net (code "32") (name "Net-(U1-IREF)") (class "Default")
      (node (ref "R1") (pin "1") (pinfunction "1_1") (pintype "passive"))
      (node (ref "U1") (pin "12") (pinfunction "IREF_12") (pintype "passive"))
    )
    (net (code "33") (name "Net-(U1-VBREF)") (class "Default")
      (node (ref "C2") (pin "1") (pinfunction "1_1") (pintype "passive"))
      (node (ref "U1") (pin "6") (pinfunction "VBREF_6") (pintype "passive"))
    )
    (net (code "34") (name "Net-(U1-VCC)") (class "Default")
      (node (ref "C7") (pin "1") (pinfunction "1_1") (pintype "passive"))
      (node (ref "U1") (pin "14") (pinfunction "VCC_14") (pintype "passive"))
    )
    (net (code "35") (name "Net-(U1-VCOMH)") (class "Default")
      (node (ref "C8") (pin "1") (pinfunction "1_1") (pintype "passive"))
      (node (ref "U1") (pin "13") (pinfunction "VCOMH_13") (pintype "passive"))
    )
    (net (code "36") (name "Net-(U1-~{RES})") (class "Default")
      (node (ref "R3") (pin "2") (pinfunction "2_2") (pintype "passive"))
      (node (ref "U1") (pin "9") (pinfunction "~{RES}_9") (pintype "passive"))
    )
    (net (code "37") (name "Net-(U2-XTAL_N)") (class "Default")
      (node (ref "C13") (pin "2") (pinfunction "2_2") (pintype "passive"))
      (node (ref "U2") (pin "29") (pinfunction "XTAL_N_29") (pintype "passive"))
      (node (ref "Y1") (pin "3") (pinfunction "X2_3") (pintype "passive"))
    )
    (net (code "38") (name "Net-(U2-XTAL_P)") (class "Default")
      (node (ref "C12") (pin "2") (pinfunction "2_2") (pintype "passive"))
      (node (ref "U2") (pin "30") (pinfunction "XTAL_P_30") (pintype "passive"))
      (node (ref "Y1") (pin "1") (pinfunction "X1_1") (pintype "passive"))
    )
    (net (code "39") (name "Net-(U3-BP)") (class "Default")
      (node (ref "C24") (pin "2") (pinfunction "2_2") (pintype "passive"))
      (node (ref "U3") (pin "4") (pinfunction "BP_4") (pintype "passive"))
    )
    (net (code "40") (name "Net-(U3-EN)") (class "Default")
      (node (ref "R9") (pin "2") (pinfunction "2_2") (pintype "passive"))
      (node (ref "U3") (pin "3") (pinfunction "EN_3") (pintype "passive"))
    )
    (net (code "41") (name "Net-(U4-RTRICK)") (class "Default")
      (node (ref "R15") (pin "2") (pinfunction "2_2") (pintype "passive"))
      (node (ref "U4") (pin "12") (pinfunction "RTRICK_12") (pintype "passive"))
    )
    (net (code "42") (name "Net-(U4-VS)") (class "Default")
      (node (ref "C27") (pin "2") (pinfunction "2_2") (pintype "passive"))
      (node (ref "C28") (pin "2") (pinfunction "2_2") (pintype "passive"))
      (node (ref "L2") (pin "1") (pinfunction "1_1") (pintype "passive"))
      (node (ref "R13") (pin "2") (pinfunction "2_2") (pintype "passive"))
      (node (ref "U4") (pin "8") (pinfunction "VS_8") (pintype "passive"))
    )
    (net (code "43") (name "Net-(USB1-CC1)") (class "Default")
      (node (ref "R8") (pin "2") (pinfunction "2_2") (pintype "passive"))
      (node (ref "USB1") (pin "A5") (pinfunction "CC1_A5") (pintype "passive"))
    )
    (net (code "44") (name "Net-(USB1-CC2)") (class "Default")
      (node (ref "R7") (pin "1") (pinfunction "1_1") (pintype "passive"))
      (node (ref "USB1") (pin "B5") (pinfunction "CC2_B5") (pintype "passive"))
    )
    (net (code "45") (name "VBUS") (class "Default")
      (node (ref "C19") (pin "2") (pinfunction "2_2") (pintype "passive"))
      (node (ref "C25") (pin "2") (pinfunction "2_2") (pintype "passive"))
      (node (ref "C26") (pin "2") (pinfunction "2_2") (pintype "passive"))
      (node (ref "Q4") (pin "3") (pinfunction "D_3") (pintype "passive"))
      (node (ref "Q5") (pin "1") (pinfunction "G_1") (pintype "passive"))
      (node (ref "R19") (pin "2") (pinfunction "2_2") (pintype "passive"))
      (node (ref "TP3") (pin "1") (pinfunction "1_1") (pintype "passive"))
      (node (ref "U4") (pin "1") (pinfunction "VIN_1") (pintype "passive"))
      (node (ref "U4") (pin "16") (pinfunction "VIN_16") (pintype "passive"))
      (node (ref "U4") (pin "4") (pinfunction "VIN_4") (pintype "passive"))
      (node (ref "U4") (pin "5") (pinfunction "VIN_5") (pintype "passive"))
      (node (ref "USB1") (pin "A4_-_B9") (pinfunction "VBUS_A4_-_B9") (pintype "passive"))
      (node (ref "USB1") (pin "A9_-_B4") (pinfunction "VBUS_A9_-_B4") (pintype "passive"))
    )
    (net (code "46") (name "VLED") (class "Default")
      (node (ref "C21") (pin "2") (pinfunction "2_2") (pintype "passive"))
      (node (ref "D2") (pin "1") (pinfunction "Cathode_1") (pintype "passive"))
      (node (ref "J3") (pin "1") (pinfunction "1_1") (pintype "passive"))
      (node (ref "Q6") (pin "3") (pinfunction "D_3") (pintype "passive"))
      (node (ref "R9") (pin "1") (pinfunction "1_1") (pintype "passive"))
      (node (ref "TP14") (pin "1") (pinfunction "1_1") (pintype "passive"))
      (node (ref "TP8") (pin "1") (pinfunction "1_1") (pintype "passive"))
      (node (ref "U3") (pin "1") (pinfunction "VIN_1") (pintype "passive"))
    )
    (net (code "47") (name "unconnected-(J2-Pad1)") (class "Default")
      (node (ref "J2") (pin "1") (pinfunction "1_1") (pintype "passive+no_connect"))
    )
    (net (code "48") (name "unconnected-(SW6-PadNC1)") (class "Default")
      (node (ref "SW6") (pin "NC1") (pintype "passive"))
    )
    (net (code "49") (name "unconnected-(SW6-PadNC2)") (class "Default")
      (node (ref "SW6") (pin "NC2") (pintype "passive"))
    )
    (net (code "50") (name "unconnected-(U2-GPIO10-Pad16)") (class "Default")
      (node (ref "U2") (pin "16") (pinfunction "GPIO10_16") (pintype "passive"))
    )
    (net (code "51") (name "unconnected-(U2-SPICLK-Pad22)") (class "Default")
      (node (ref "U2") (pin "22") (pinfunction "SPICLK_22") (pintype "passive"))
    )
    (net (code "52") (name "unconnected-(U2-SPICS0-Pad21)") (class "Default")
      (node (ref "U2") (pin "21") (pinfunction "SPICS0_21") (pintype "passive"))
    )
    (net (code "53") (name "unconnected-(U2-SPID-Pad23)") (class "Default")
      (node (ref "U2") (pin "23") (pinfunction "SPID_23") (pintype "passive"))
    )
    (net (code "54") (name "unconnected-(U2-SPIHD-Pad19)") (class "Default")
      (node (ref "U2") (pin "19") (pinfunction "SPIHD_19") (pintype "passive"))
    )
    (net (code "55") (name "unconnected-(U2-SPIQ-Pad24)") (class "Default")
      (node (ref "U2") (pin "24") (pinfunction "SPIQ_24") (pintype "passive"))
    )
    (net (code "56") (name "unconnected-(U2-SPIWP-Pad20)") (class "Default")
      (node (ref "U2") (pin "20") (pinfunction "SPIWP_20") (pintype "passive"))
    )
    (net (code "57") (name "unconnected-(U2-U0RXD-Pad27)") (class "Default")
      (node (ref "U2") (pin "27") (pinfunction "U0RXD_27") (pintype "passive"))
    )
    (net (code "58") (name "unconnected-(U2-U0TXD-Pad28)") (class "Default")
      (node (ref "U2") (pin "28") (pinfunction "U0TXD_28") (pintype "passive"))
    )
    (net (code "59") (name "unconnected-(U2-VDD_SPI-Pad18)") (class "Default")
      (node (ref "U2") (pin "18") (pinfunction "VDD_SPI_18") (pintype "passive"))
    )
    (net (code "60") (name "unconnected-(U4-CS-Pad13)") (class "Default")
      (node (ref "U4") (pin "13") (pinfunction "CS_13") (pintype "passive+no_connect"))
    )
    (net (code "61") (name "unconnected-(U4-~{STDBY}-Pad14)") (class "Default")
      (node (ref "U4") (pin "14") (pinfunction "~{STDBY}_14") (pintype "passive+no_connect"))
    )
    (net (code "62") (name "unconnected-(USB1-SBU1-PadA8)") (class "Default")
      (node (ref "USB1") (pin "A8") (pinfunction "SBU1_A8") (pintype "passive+no_connect"))
    )
    (net (code "63") (name "unconnected-(USB1-SBU2-PadB8)") (class "Default")
      (node (ref "USB1") (pin "B8") (pinfunction "SBU2_B8") (pintype "passive+no_connect"))
    )
  )
)
